# VALVEBOARD_ValveInterface.net
KiCad netlist of a schematic drawn in Altium Designer
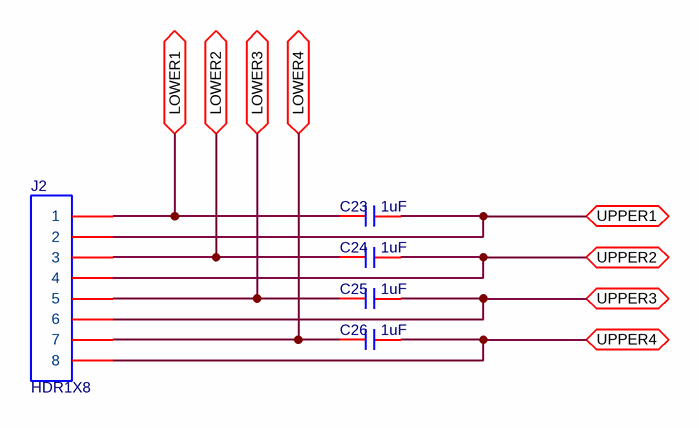
[diagram p0: VALVEBOARD_ValveInterface.SchDoc]

(export (version "E")
  (design (tool "Eeschema 10.0.6"))
  (components
    (comp (ref "C23")
      (value "1uF")
      (footprint "zynq:C0805")
      (fields (field (name "VOLTAGE") "25V") (field (name "Comment") "C-NOMO"))
      (libsource (lib "zynq") (part "C-NOMO"))
    )
    (comp (ref "C24")
      (value "1uF")
      (footprint "zynq:C0805")
      (fields (field (name "VOLTAGE") "25V") (field (name "Comment") "C-NOMO"))
      (libsource (lib "zynq") (part "C-NOMO"))
    )
    (comp (ref "C25")
      (value "1uF")
      (footprint "zynq:C0805")
      (fields (field (name "VOLTAGE") "25V") (field (name "Comment") "C-NOMO"))
      (libsource (lib "zynq") (part "C-NOMO"))
    )
    (comp (ref "C26")
      (value "1uF")
      (footprint "zynq:C0805")
      (fields (field (name "VOLTAGE") "25V") (field (name "Comment") "C-NOMO"))
      (libsource (lib "zynq") (part "C-NOMO"))
    )
    (comp (ref "J2") (value "HDR1X8") (footprint "KF15EDGK-3.81-8P") (libsource (lib "zynq") (part "HDR1X8")))
  )
  (nets
    (net (code "1") (name "/LOWER1") (class "Default")
      (node (ref "C23") (pin "2") (pinfunction "2_2") (pintype "passive"))
      (node (ref "J2") (pin "1") (pinfunction "1_1") (pintype "passive"))
    )
    (net (code "2") (name "/LOWER2") (class "Default")
      (node (ref "C24") (pin "2") (pinfunction "2_2") (pintype "passive"))
      (node (ref "J2") (pin "3") (pinfunction "3_3") (pintype "passive"))
    )
    (net (code "3") (name "/LOWER3") (class "Default")
      (node (ref "C25") (pin "2") (pinfunction "2_2") (pintype "passive"))
      (node (ref "J2") (pin "5") (pinfunction "5_5") (pintype "passive"))
    )
    (net (code "4") (name "/LOWER4") (class "Default")
      (node (ref "C26") (pin "2") (pinfunction "2_2") (pintype "passive"))
      (node (ref "J2") (pin "7") (pinfunction "7_7") (pintype "passive"))
    )
    (net (code "5") (name "/UPPER1") (class "Default")
      (node (ref "C23") (pin "1") (pinfunction "1_1") (pintype "passive"))
      (node (ref "J2") (pin "2") (pinfunction "2_2") (pintype "passive"))
    )
    (net (code "6") (name "/UPPER2") (class "Default")
      (node (ref "C24") (pin "1") (pinfunction "1_1") (pintype "passive"))
      (node (ref "J2") (pin "4") (pinfunction "4_4") (pintype "passive"))
    )
    (net (code "7") (name "/UPPER3") (class "Default")
      (node (ref "C25") (pin "1") (pinfunction "1_1") (pintype "passive"))
      (node (ref "J2") (pin "6") (pinfunction "6_6") (pintype "passive"))
    )
    (net (code "8") (name "/UPPER4") (class "Default")
      (node (ref "C26") (pin "1") (pinfunction "1_1") (pintype "passive"))
      (node (ref "J2") (pin "8") (pinfunction "8_8") (pintype "passive"))
    )
  )
)
